# flight_controller_initial.net
KiCad netlist of a schematic drawn in EAGLE
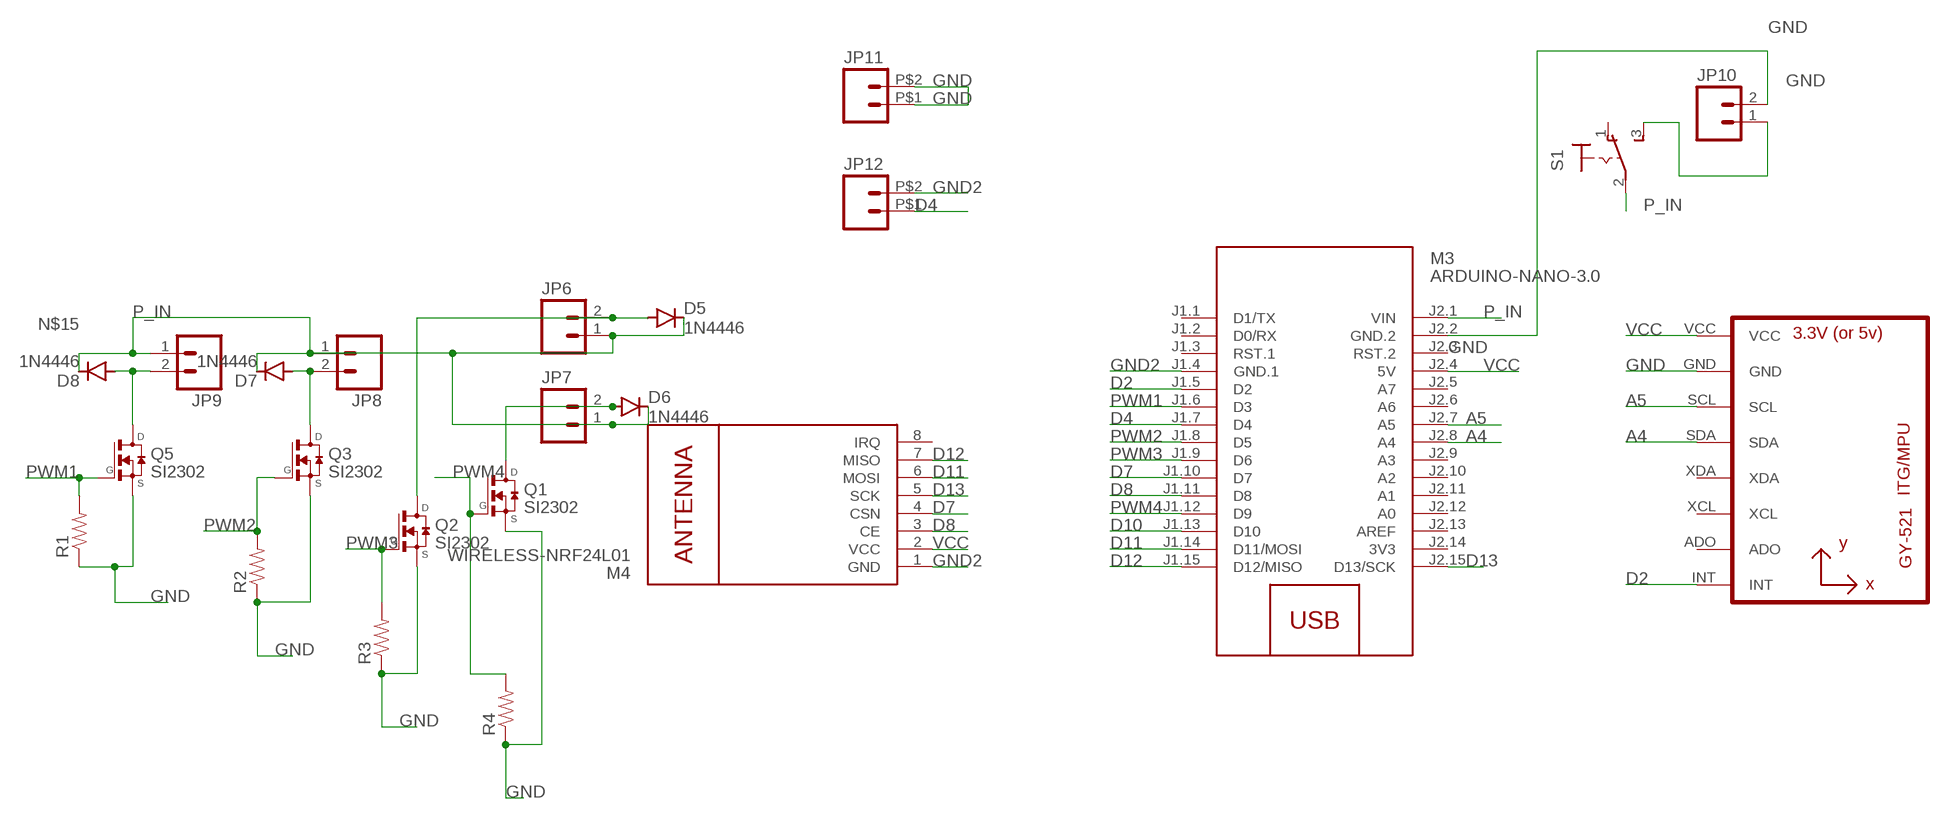
[diagram p0: schematic, sheet 1]

(export (version "E")
  (design (tool "Eeschema 10.0.6"))
  (components
    (comp (ref "D5")
      (value "1N4446")
      (footprint "eagle-import:DO35-10")
      (libsource (lib "eagle-import") (part "1N4446"))
    )
    (comp (ref "D6")
      (value "1N4446")
      (footprint "eagle-import:DO35-10")
      (libsource (lib "eagle-import") (part "1N4446"))
    )
    (comp (ref "D7")
      (value "1N4446")
      (footprint "eagle-import:DO35-10")
      (libsource (lib "eagle-import") (part "1N4446"))
    )
    (comp (ref "D8")
      (value "1N4446")
      (footprint "eagle-import:DO35-10")
      (libsource (lib "eagle-import") (part "1N4446"))
    )
    (comp (ref "JP6")
      (value "M021X02_NO_SILK")
      (footprint "eagle-import:1X02_NO_SILK")
      (libsource (lib "eagle-import") (part "M021X02_NO_SILK"))
    )
    (comp (ref "JP7")
      (value "M021X02_NO_SILK")
      (footprint "eagle-import:1X02_NO_SILK")
      (libsource (lib "eagle-import") (part "M021X02_NO_SILK"))
    )
    (comp (ref "JP8")
      (value "M021X02_NO_SILK")
      (footprint "eagle-import:1X02_NO_SILK")
      (libsource (lib "eagle-import") (part "M021X02_NO_SILK"))
    )
    (comp (ref "JP9")
      (value "M021X02_NO_SILK")
      (footprint "eagle-import:1X02_NO_SILK")
      (libsource (lib "eagle-import") (part "M021X02_NO_SILK"))
    )
    (comp (ref "JP10")
      (value "M02PTH")
      (footprint "eagle-import:1X02")
      (libsource (lib "eagle-import") (part "M02PTH"))
    )
    (comp (ref "JP11")
      (value "M02PTH2")
      (footprint "eagle-import:1X02_BIG")
      (libsource (lib "eagle-import") (part "M02PTH2"))
    )
    (comp (ref "JP12")
      (value "M02PTH2")
      (footprint "eagle-import:1X02_BIG")
      (libsource (lib "eagle-import") (part "M02PTH2"))
    )
    (comp (ref "M3")
      (value "ARDUINO-NANO-3.0")
      (footprint "eagle-import:ARDUINO-NANO-3.0")
      (libsource (lib "eagle-import") (part "ARDUINO-NANO-3.0"))
    )
    (comp (ref "M4")
      (value "WIRELESS-NRF24L01")
      (footprint "eagle-import:WIRELESS-NRF24L01")
      (libsource (lib "eagle-import") (part "WIRELESS-NRF24L01"))
    )
    (comp (ref "Q1")
      (value "SI2302")
      (footprint "eagle-import:SOT23")
      (libsource (lib "eagle-import") (part "SI2302"))
    )
    (comp (ref "Q2")
      (value "SI2302")
      (footprint "eagle-import:SOT23")
      (libsource (lib "eagle-import") (part "SI2302"))
    )
    (comp (ref "Q3")
      (value "SI2302")
      (footprint "eagle-import:SOT23")
      (libsource (lib "eagle-import") (part "SI2302"))
    )
    (comp (ref "Q5")
      (value "SI2302")
      (footprint "eagle-import:SOT23")
      (libsource (lib "eagle-import") (part "SI2302"))
    )
    (comp (ref "R1")
      (value "RESISTORAXIAL-0.3")
      (footprint "eagle-import:AXIAL-0.3")
      (libsource (lib "eagle-import") (part "RESISTORAXIAL-0.3"))
    )
    (comp (ref "R2")
      (value "RESISTORAXIAL-0.3")
      (footprint "eagle-import:AXIAL-0.3")
      (libsource (lib "eagle-import") (part "RESISTORAXIAL-0.3"))
    )
    (comp (ref "R3")
      (value "RESISTORAXIAL-0.3")
      (footprint "eagle-import:AXIAL-0.3")
      (libsource (lib "eagle-import") (part "RESISTORAXIAL-0.3"))
    )
    (comp (ref "R4")
      (value "RESISTORAXIAL-0.3")
      (footprint "eagle-import:AXIAL-0.3")
      (libsource (lib "eagle-import") (part "RESISTORAXIAL-0.3"))
    )
    (comp (ref "S1")
      (value "M9040P")
      (footprint "eagle-import:M9040P")
      (libsource (lib "eagle-import") (part "M9040P"))
    )
    (comp (ref "U2")
      (value "GY-521MPU6050")
      (footprint "eagle-import:GY-521")
      (libsource (lib "eagle-import") (part "GY-521MPU6050"))
    )
  )
  (nets
    (net (code "1") (name "/3V3") (class "Default")
      (node (ref "M3") (pin "J2.14") (pinfunction "3V3_J2.14") (pintype "power_in"))
    )
    (net (code "2") (name "/A4") (class "Default")
      (node (ref "M3") (pin "J2.8") (pinfunction "A4_J2.8") (pintype "bidirectional"))
      (node (ref "U2") (pin "SDA") (pinfunction "SDA_SDA") (pintype "bidirectional"))
    )
    (net (code "3") (name "/A5") (class "Default")
      (node (ref "M3") (pin "J2.7") (pinfunction "A5_J2.7") (pintype "bidirectional"))
      (node (ref "U2") (pin "SCL") (pinfunction "SCL_SCL") (pintype "bidirectional"))
    )
    (net (code "4") (name "/D2") (class "Default")
      (node (ref "M3") (pin "J1.5") (pinfunction "D2_J1.5") (pintype "bidirectional"))
      (node (ref "U2") (pin "INT") (pinfunction "INT_INT") (pintype "bidirectional"))
    )
    (net (code "5") (name "/D4") (class "Default")
      (node (ref "JP12") (pin "P$1") (pinfunction "1_P$1") (pintype "passive"))
      (node (ref "M3") (pin "J1.7") (pinfunction "D4_J1.7") (pintype "bidirectional"))
    )
    (net (code "6") (name "/D7") (class "Default")
      (node (ref "M3") (pin "J1.10") (pinfunction "D7_J1.10") (pintype "bidirectional"))
      (node (ref "M4") (pin "4") (pinfunction "CSN_4") (pintype "bidirectional"))
    )
    (net (code "7") (name "/D8") (class "Default")
      (node (ref "M3") (pin "J1.11") (pinfunction "D8_J1.11") (pintype "bidirectional"))
      (node (ref "M4") (pin "3") (pinfunction "CE_3") (pintype "bidirectional"))
    )
    (net (code "8") (name "/D10") (class "Default")
      (node (ref "M3") (pin "J1.13") (pinfunction "D10_J1.13") (pintype "bidirectional"))
    )
    (net (code "9") (name "/D11") (class "Default")
      (node (ref "M3") (pin "J1.14") (pinfunction "D11/MOSI_J1.14") (pintype "bidirectional"))
      (node (ref "M4") (pin "6") (pinfunction "MOSI_6") (pintype "bidirectional"))
    )
    (net (code "10") (name "/D12") (class "Default")
      (node (ref "M3") (pin "J1.15") (pinfunction "D12/MISO_J1.15") (pintype "bidirectional"))
      (node (ref "M4") (pin "7") (pinfunction "MISO_7") (pintype "bidirectional"))
    )
    (net (code "11") (name "/D13") (class "Default")
      (node (ref "M3") (pin "J2.15") (pinfunction "D13/SCK_J2.15") (pintype "bidirectional"))
      (node (ref "M4") (pin "5") (pinfunction "SCK_5") (pintype "bidirectional"))
    )
    (net (code "12") (name "/GND") (class "Default")
      (node (ref "JP10") (pin "2") (pinfunction "2_2") (pintype "passive"))
      (node (ref "JP11") (pin "P$1") (pinfunction "1_P$1") (pintype "passive"))
      (node (ref "JP11") (pin "P$2") (pinfunction "2_P$2") (pintype "passive"))
      (node (ref "M3") (pin "J2.2") (pinfunction "GND.2_J2.2") (pintype "power_in"))
      (node (ref "Q1") (pin "2") (pinfunction "S_2") (pintype "passive"))
      (node (ref "Q2") (pin "2") (pinfunction "S_2") (pintype "passive"))
      (node (ref "Q3") (pin "2") (pinfunction "S_2") (pintype "passive"))
      (node (ref "Q5") (pin "2") (pinfunction "S_2") (pintype "passive"))
      (node (ref "R1") (pin "P$1") (pinfunction "1_P$1") (pintype "passive"))
      (node (ref "R2") (pin "P$1") (pinfunction "1_P$1") (pintype "passive"))
      (node (ref "R3") (pin "P$1") (pinfunction "1_P$1") (pintype "passive"))
      (node (ref "R4") (pin "P$1") (pinfunction "1_P$1") (pintype "passive"))
      (node (ref "U2") (pin "GND") (pinfunction "GND_GND") (pintype "bidirectional"))
    )
    (net (code "13") (name "/GND2") (class "Default")
      (node (ref "JP12") (pin "P$2") (pinfunction "2_P$2") (pintype "passive"))
      (node (ref "M3") (pin "J1.4") (pinfunction "GND.1_J1.4") (pintype "power_in"))
      (node (ref "M4") (pin "1") (pinfunction "GND_1") (pintype "power_in"))
    )
    (net (code "14") (name "/N$15") (class "Default")
      (node (ref "D8") (pin "A") (pinfunction "A_A") (pintype "passive"))
      (node (ref "JP9") (pin "2") (pinfunction "2_2") (pintype "passive"))
      (node (ref "Q5") (pin "3") (pinfunction "D_3") (pintype "passive"))
    )
    (net (code "15") (name "/PWM1") (class "Default")
      (node (ref "M3") (pin "J1.6") (pinfunction "D3_J1.6") (pintype "bidirectional"))
      (node (ref "Q5") (pin "1") (pinfunction "G_1") (pintype "passive"))
      (node (ref "R1") (pin "P$2") (pinfunction "2_P$2") (pintype "passive"))
    )
    (net (code "16") (name "/PWM2") (class "Default")
      (node (ref "M3") (pin "J1.8") (pinfunction "D5_J1.8") (pintype "bidirectional"))
      (node (ref "Q3") (pin "1") (pinfunction "G_1") (pintype "passive"))
      (node (ref "R2") (pin "P$2") (pinfunction "2_P$2") (pintype "passive"))
    )
    (net (code "17") (name "/PWM3") (class "Default")
      (node (ref "M3") (pin "J1.9") (pinfunction "D6_J1.9") (pintype "bidirectional"))
      (node (ref "Q2") (pin "1") (pinfunction "G_1") (pintype "passive"))
      (node (ref "R3") (pin "P$2") (pinfunction "2_P$2") (pintype "passive"))
    )
    (net (code "18") (name "/PWM4") (class "Default")
      (node (ref "M3") (pin "J1.12") (pinfunction "D9_J1.12") (pintype "bidirectional"))
      (node (ref "Q1") (pin "1") (pinfunction "G_1") (pintype "passive"))
      (node (ref "R4") (pin "P$2") (pinfunction "2_P$2") (pintype "passive"))
    )
    (net (code "19") (name "/P_IN") (class "Default")
      (node (ref "D5") (pin "C") (pinfunction "C_C") (pintype "passive"))
      (node (ref "D6") (pin "C") (pinfunction "C_C") (pintype "passive"))
      (node (ref "D7") (pin "C") (pinfunction "C_C") (pintype "passive"))
      (node (ref "D8") (pin "C") (pinfunction "C_C") (pintype "passive"))
      (node (ref "JP6") (pin "1") (pinfunction "1_1") (pintype "passive"))
      (node (ref "JP7") (pin "1") (pinfunction "1_1") (pintype "passive"))
      (node (ref "JP8") (pin "1") (pinfunction "1_1") (pintype "passive"))
      (node (ref "JP9") (pin "1") (pinfunction "1_1") (pintype "passive"))
      (node (ref "M3") (pin "J2.1") (pinfunction "VIN_J2.1") (pintype "power_in"))
      (node (ref "S1") (pin "2") (pinfunction "P_2") (pintype "passive"))
    )
    (net (code "20") (name "/VCC") (class "Default")
      (node (ref "M3") (pin "J2.4") (pinfunction "5V_J2.4") (pintype "power_in"))
      (node (ref "M4") (pin "2") (pinfunction "VCC_2") (pintype "power_in"))
      (node (ref "U2") (pin "VCC") (pinfunction "VCC_VCC") (pintype "bidirectional"))
    )
    (net (code "21") (name "Net-(Q1-D)") (class "Default")
      (node (ref "D6") (pin "A") (pinfunction "A_A") (pintype "passive"))
      (node (ref "JP7") (pin "2") (pinfunction "2_2") (pintype "passive"))
      (node (ref "Q1") (pin "3") (pinfunction "D_3") (pintype "passive"))
    )
    (net (code "22") (name "Net-(Q2-D)") (class "Default")
      (node (ref "D5") (pin "A") (pinfunction "A_A") (pintype "passive"))
      (node (ref "JP6") (pin "2") (pinfunction "2_2") (pintype "passive"))
      (node (ref "Q2") (pin "3") (pinfunction "D_3") (pintype "passive"))
    )
    (net (code "23") (name "Net-(Q3-D)") (class "Default")
      (node (ref "D7") (pin "A") (pinfunction "A_A") (pintype "passive"))
      (node (ref "JP8") (pin "2") (pinfunction "2_2") (pintype "passive"))
      (node (ref "Q3") (pin "3") (pinfunction "D_3") (pintype "passive"))
    )
    (net (code "24") (name "Net-(S1-S)") (class "Default")
      (node (ref "JP10") (pin "1") (pinfunction "1_1") (pintype "passive"))
      (node (ref "S1") (pin "3") (pinfunction "S_3") (pintype "passive"))
    )
    (net (code "25") (name "unconnected-(M3-A0-PadJ2.12)") (class "Default")
      (node (ref "M3") (pin "J2.12") (pinfunction "A0_J2.12") (pintype "bidirectional"))
    )
    (net (code "26") (name "unconnected-(M3-A1-PadJ2.11)") (class "Default")
      (node (ref "M3") (pin "J2.11") (pinfunction "A1_J2.11") (pintype "bidirectional"))
    )
    (net (code "27") (name "unconnected-(M3-A2-PadJ2.10)") (class "Default")
      (node (ref "M3") (pin "J2.10") (pinfunction "A2_J2.10") (pintype "bidirectional"))
    )
    (net (code "28") (name "unconnected-(M3-A3-PadJ2.9)") (class "Default")
      (node (ref "M3") (pin "J2.9") (pinfunction "A3_J2.9") (pintype "bidirectional"))
    )
    (net (code "29") (name "unconnected-(M3-A6-PadJ2.6)") (class "Default")
      (node (ref "M3") (pin "J2.6") (pinfunction "A6_J2.6") (pintype "bidirectional"))
    )
    (net (code "30") (name "unconnected-(M3-A7-PadJ2.5)") (class "Default")
      (node (ref "M3") (pin "J2.5") (pinfunction "A7_J2.5") (pintype "bidirectional"))
    )
    (net (code "31") (name "unconnected-(M3-AREF-PadJ2.13)") (class "Default")
      (node (ref "M3") (pin "J2.13") (pinfunction "AREF_J2.13") (pintype "bidirectional"))
    )
    (net (code "32") (name "unconnected-(M3-D0{slash}RX-PadJ1.2)") (class "Default")
      (node (ref "M3") (pin "J1.2") (pinfunction "D0/RX_J1.2") (pintype "bidirectional"))
    )
    (net (code "33") (name "unconnected-(M3-D1{slash}TX-PadJ1.1)") (class "Default")
      (node (ref "M3") (pin "J1.1") (pinfunction "D1/TX_J1.1") (pintype "bidirectional"))
    )
    (net (code "34") (name "unconnected-(M3-RST.1-PadJ1.3)") (class "Default")
      (node (ref "M3") (pin "J1.3") (pinfunction "RST.1_J1.3") (pintype "bidirectional"))
    )
    (net (code "35") (name "unconnected-(M3-RST.2-PadJ2.3)") (class "Default")
      (node (ref "M3") (pin "J2.3") (pinfunction "RST.2_J2.3") (pintype "bidirectional"))
    )
    (net (code "36") (name "unconnected-(M4-IRQ-Pad8)") (class "Default")
      (node (ref "M4") (pin "8") (pinfunction "IRQ_8") (pintype "bidirectional"))
    )
    (net (code "37") (name "unconnected-(S1-O-Pad1)") (class "Default")
      (node (ref "S1") (pin "1") (pinfunction "O_1") (pintype "passive"))
    )
    (net (code "38") (name "unconnected-(U2-PadADO)") (class "Default")
      (node (ref "U2") (pin "ADO") (pinfunction "ADO_ADO") (pintype "bidirectional"))
    )
    (net (code "39") (name "unconnected-(U2-PadXCL)") (class "Default")
      (node (ref "U2") (pin "XCL") (pinfunction "XCL_XCL") (pintype "bidirectional"))
    )
    (net (code "40") (name "unconnected-(U2-PadXDA)") (class "Default")
      (node (ref "U2") (pin "XDA") (pinfunction "XDA_XDA") (pintype "bidirectional"))
    )
  )
)
